# H4_PadController_Rev_2.net
KiCad netlist of a schematic drawn in EAGLE
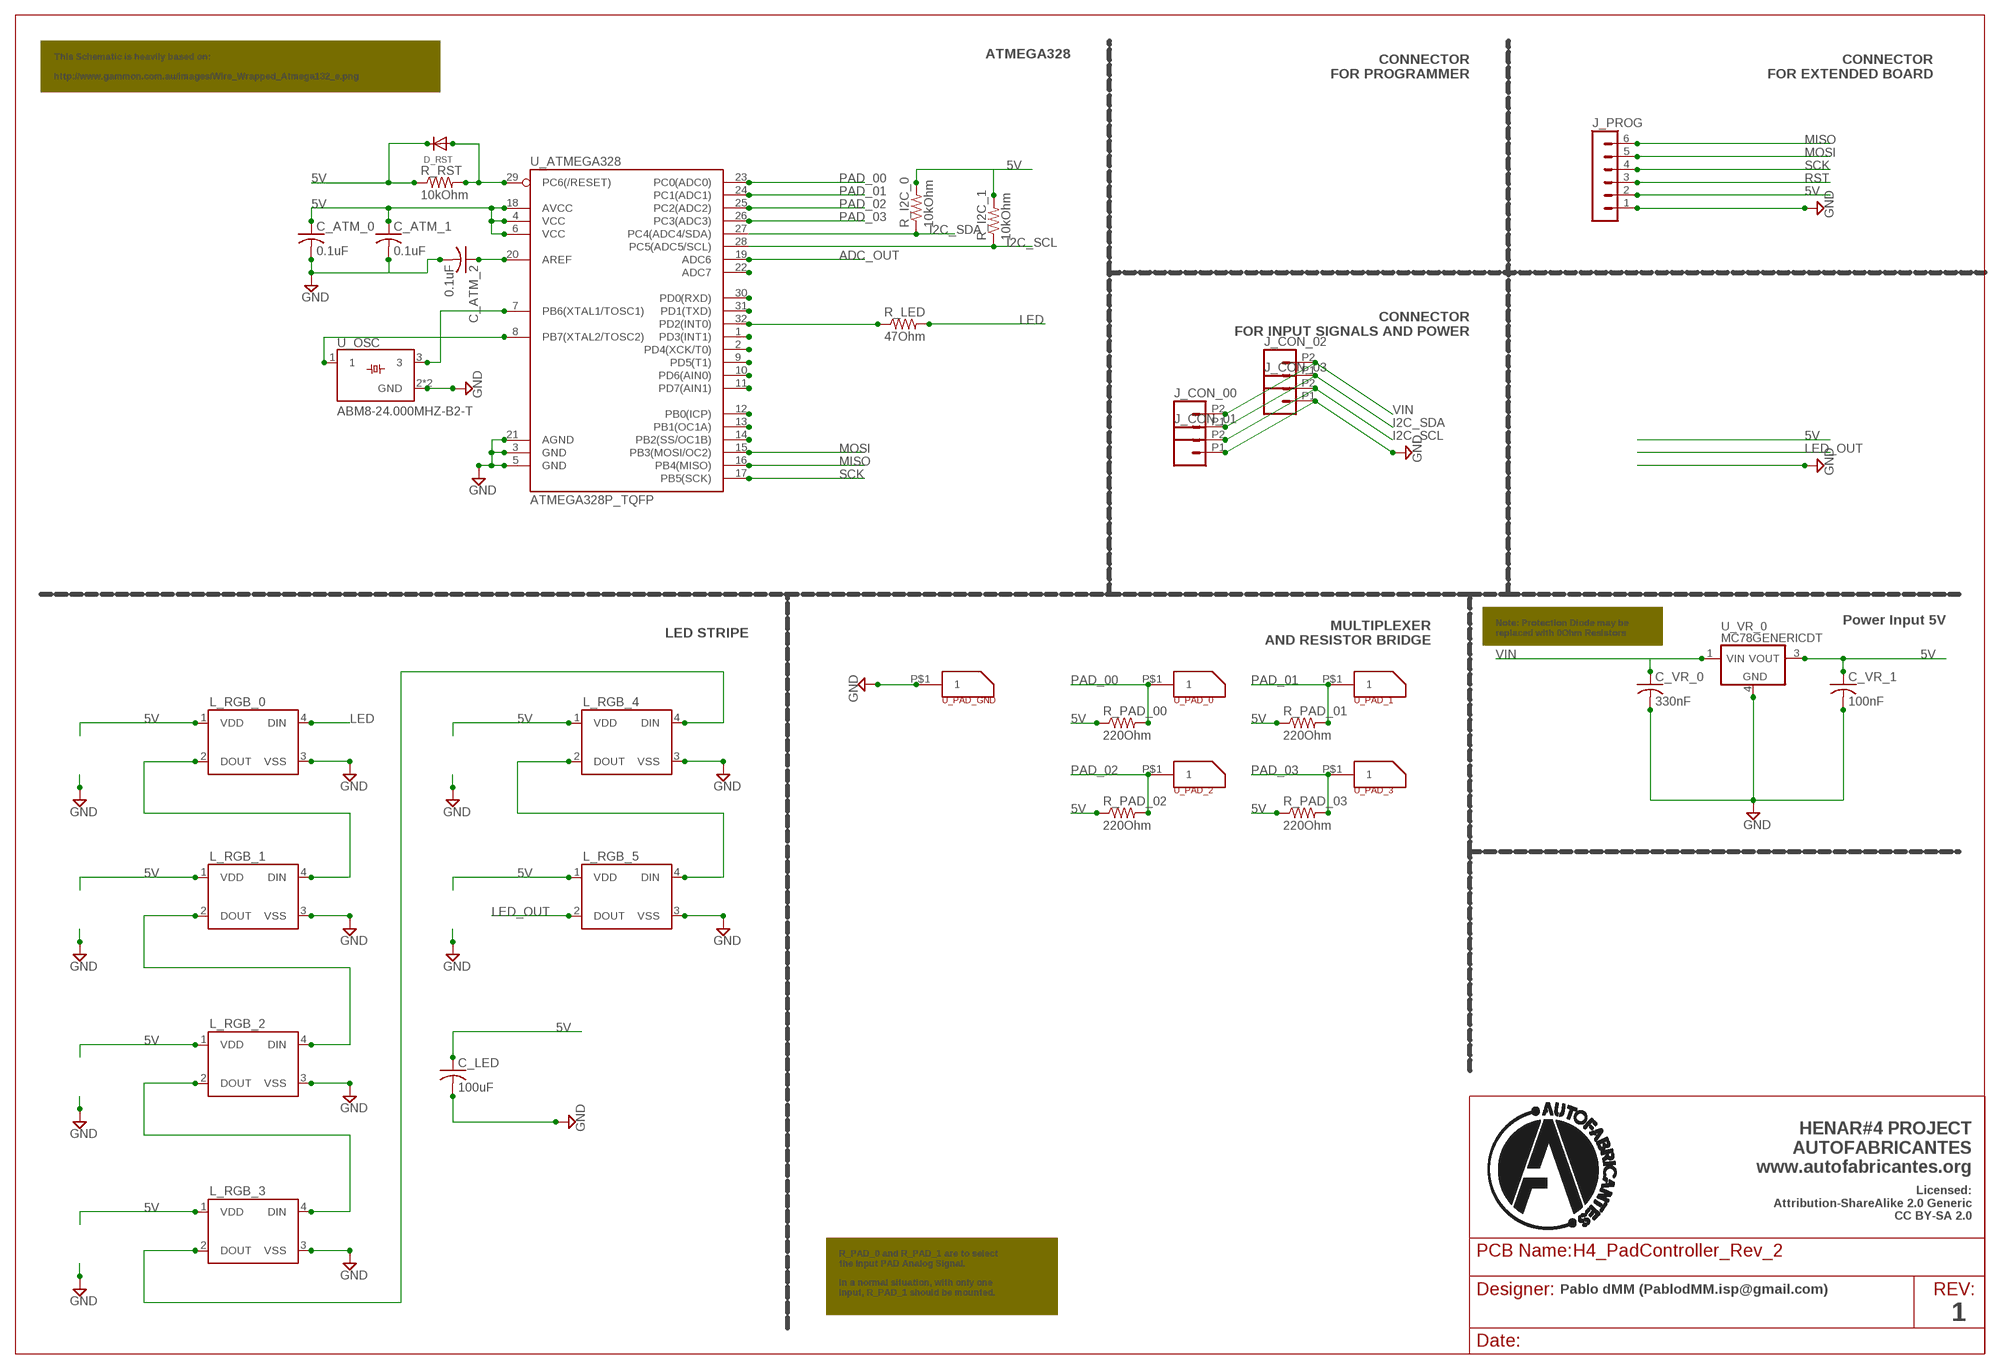
[diagram p0: schematic, sheet 1]

(export (version "E")
  (design (tool "Eeschema 10.0.6"))
  (components
    (comp (ref "C_ATM_0")
      (value "0.1uF")
      (footprint "eagle-import:C0805")
      (libsource (lib "eagle-import") (part "C-USC0805"))
    )
    (comp (ref "C_ATM_1")
      (value "0.1uF")
      (footprint "eagle-import:C0805")
      (libsource (lib "eagle-import") (part "C-USC0805"))
    )
    (comp (ref "C_ATM_2")
      (value "0.1uF")
      (footprint "eagle-import:C0805")
      (libsource (lib "eagle-import") (part "C-USC0805"))
    )
    (comp (ref "C_LED")
      (value "100uF")
      (footprint "eagle-import:C1210")
      (libsource (lib "eagle-import") (part "C-USC1210"))
    )
    (comp (ref "C_VR_0")
      (value "330nF")
      (footprint "eagle-import:C0805")
      (libsource (lib "eagle-import") (part "C-USC0805"))
    )
    (comp (ref "C_VR_1")
      (value "100nF")
      (footprint "eagle-import:C0805")
      (libsource (lib "eagle-import") (part "C-USC0805"))
    )
    (comp (ref "D_RST")
      (value "DIODESOD-123")
      (footprint "eagle-import:SOD-123")
      (libsource (lib "eagle-import") (part "DIODESOD-123"))
    )
    (comp (ref "J_CON_00")
      (value "M022.54MM_SCREWTERM")
      (footprint "eagle-import:1X02_2.54_SCREWTERM")
      (libsource (lib "eagle-import") (part "M022.54MM_SCREWTERM"))
    )
    (comp (ref "J_CON_01")
      (value "M022.54MM_SCREWTERM")
      (footprint "eagle-import:1X02_2.54_SCREWTERM")
      (libsource (lib "eagle-import") (part "M022.54MM_SCREWTERM"))
    )
    (comp (ref "J_CON_02")
      (value "M022.54MM_SCREWTERM")
      (footprint "eagle-import:1X02_2.54_SCREWTERM")
      (libsource (lib "eagle-import") (part "M022.54MM_SCREWTERM"))
    )
    (comp (ref "J_CON_03")
      (value "M022.54MM_SCREWTERM")
      (footprint "eagle-import:1X02_2.54_SCREWTERM")
      (libsource (lib "eagle-import") (part "M022.54MM_SCREWTERM"))
    )
    (comp (ref "J_PROG")
      (value "MA06-1")
      (footprint "eagle-import:MA06-1")
      (libsource (lib "eagle-import") (part "MA06-1"))
    )
    (comp (ref "L_RGB_0")
      (value "WS2812B")
      (footprint "eagle-import:WS2812B")
      (libsource (lib "eagle-import") (part "WS2812B"))
    )
    (comp (ref "L_RGB_1")
      (value "WS2812B")
      (footprint "eagle-import:WS2812B")
      (libsource (lib "eagle-import") (part "WS2812B"))
    )
    (comp (ref "L_RGB_2")
      (value "WS2812B")
      (footprint "eagle-import:WS2812B")
      (libsource (lib "eagle-import") (part "WS2812B"))
    )
    (comp (ref "L_RGB_3")
      (value "WS2812B")
      (footprint "eagle-import:WS2812B")
      (libsource (lib "eagle-import") (part "WS2812B"))
    )
    (comp (ref "L_RGB_4")
      (value "WS2812B")
      (footprint "eagle-import:WS2812B")
      (libsource (lib "eagle-import") (part "WS2812B"))
    )
    (comp (ref "L_RGB_5")
      (value "WS2812B")
      (footprint "eagle-import:WS2812B")
      (libsource (lib "eagle-import") (part "WS2812B"))
    )
    (comp (ref "R_I2C_0")
      (value "10kOhm")
      (footprint "eagle-import:M0805")
      (libsource (lib "eagle-import") (part "R-US_M0805"))
    )
    (comp (ref "R_I2C_1")
      (value "10kOhm")
      (footprint "eagle-import:M0805")
      (libsource (lib "eagle-import") (part "R-US_M0805"))
    )
    (comp (ref "R_LED")
      (value "47Ohm")
      (footprint "eagle-import:M0805")
      (libsource (lib "eagle-import") (part "R-US_M0805"))
    )
    (comp (ref "R_PAD_00")
      (value "220Ohm")
      (footprint "eagle-import:M0805")
      (libsource (lib "eagle-import") (part "R-US_M0805"))
    )
    (comp (ref "R_PAD_01")
      (value "220Ohm")
      (footprint "eagle-import:M0805")
      (libsource (lib "eagle-import") (part "R-US_M0805"))
    )
    (comp (ref "R_PAD_02")
      (value "220Ohm")
      (footprint "eagle-import:M0805")
      (libsource (lib "eagle-import") (part "R-US_M0805"))
    )
    (comp (ref "R_PAD_03")
      (value "220Ohm")
      (footprint "eagle-import:M0805")
      (libsource (lib "eagle-import") (part "R-US_M0805"))
    )
    (comp (ref "R_RST")
      (value "10kOhm")
      (footprint "eagle-import:M0805")
      (libsource (lib "eagle-import") (part "R-US_M0805"))
    )
    (comp (ref "U_ATMEGA328")
      (value "ATMEGA328P_TQFP")
      (footprint "eagle-import:TQFP32-08")
      (libsource (lib "eagle-import") (part "ATMEGA328P_TQFP"))
    )
    (comp (ref "U_OSC")
      (value "ABM8-24.000MHZ-B2-T")
      (footprint "eagle-import:OSCSC320X250X100N")
      (fields (field (name "MF") "Abracon"))
      (libsource (lib "eagle-import") (part "ABM8-24.000MHZ-B2-T"))
    )
    (comp (ref "U_PAD_0")
      (value "PAD_CONNECTOR_MULTI")
      (footprint "eagle-import:PAD_CONNECTOR_MULTI")
      (libsource (lib "eagle-import") (part "PAD_CONNECTOR_MULTI"))
    )
    (comp (ref "U_PAD_1")
      (value "PAD_CONNECTOR_MULTI")
      (footprint "eagle-import:PAD_CONNECTOR_MULTI")
      (libsource (lib "eagle-import") (part "PAD_CONNECTOR_MULTI"))
    )
    (comp (ref "U_PAD_2")
      (value "PAD_CONNECTOR_MULTI")
      (footprint "eagle-import:PAD_CONNECTOR_MULTI")
      (libsource (lib "eagle-import") (part "PAD_CONNECTOR_MULTI"))
    )
    (comp (ref "U_PAD_3")
      (value "PAD_CONNECTOR_MULTI")
      (footprint "eagle-import:PAD_CONNECTOR_MULTI")
      (libsource (lib "eagle-import") (part "PAD_CONNECTOR_MULTI"))
    )
    (comp (ref "U_PAD_GND")
      (value "PAD_CONNECTOR_MULTI")
      (footprint "eagle-import:PAD_CONNECTOR_MULTI")
      (libsource (lib "eagle-import") (part "PAD_CONNECTOR_MULTI"))
    )
    (comp (ref "U_VR_0")
      (value "MC78GENERICDT")
      (footprint "eagle-import:DPAK-3")
      (libsource (lib "eagle-import") (part "MC78DTGENERIC"))
    )
  )
  (nets
    (net (code "1") (name "/5V") (class "Default")
      (node (ref "C_ATM_0") (pin "1") (pinfunction "1_1") (pintype "passive"))
      (node (ref "C_ATM_1") (pin "1") (pinfunction "1_1") (pintype "passive"))
      (node (ref "C_LED") (pin "1") (pinfunction "1_1") (pintype "passive"))
      (node (ref "C_VR_1") (pin "1") (pinfunction "1_1") (pintype "passive"))
      (node (ref "D_RST") (pin "C") (pinfunction "C_C") (pintype "passive"))
      (node (ref "J_PROG") (pin "2") (pinfunction "2_2") (pintype "passive"))
      (node (ref "L_RGB_0") (pin "1") (pinfunction "VDD_1") (pintype "power_in"))
      (node (ref "L_RGB_1") (pin "1") (pinfunction "VDD_1") (pintype "power_in"))
      (node (ref "L_RGB_2") (pin "1") (pinfunction "VDD_1") (pintype "power_in"))
      (node (ref "L_RGB_3") (pin "1") (pinfunction "VDD_1") (pintype "power_in"))
      (node (ref "L_RGB_4") (pin "1") (pinfunction "VDD_1") (pintype "power_in"))
      (node (ref "L_RGB_5") (pin "1") (pinfunction "VDD_1") (pintype "power_in"))
      (node (ref "R_I2C_0") (pin "2") (pinfunction "2_2") (pintype "passive"))
      (node (ref "R_I2C_1") (pin "2") (pinfunction "2_2") (pintype "passive"))
      (node (ref "R_PAD_00") (pin "1") (pinfunction "1_1") (pintype "passive"))
      (node (ref "R_PAD_01") (pin "1") (pinfunction "1_1") (pintype "passive"))
      (node (ref "R_PAD_02") (pin "1") (pinfunction "1_1") (pintype "passive"))
      (node (ref "R_PAD_03") (pin "1") (pinfunction "1_1") (pintype "passive"))
      (node (ref "R_RST") (pin "1") (pinfunction "1_1") (pintype "passive"))
      (node (ref "U_ATMEGA328") (pin "18") (pinfunction "AVCC_18") (pintype "bidirectional"))
      (node (ref "U_ATMEGA328") (pin "4") (pinfunction "VCC_4") (pintype "bidirectional"))
      (node (ref "U_ATMEGA328") (pin "6") (pinfunction "VCC_6") (pintype "bidirectional"))
      (node (ref "U_VR_0") (pin "3") (pinfunction "VOUT_3") (pintype "power_in"))
    )
    (net (code "2") (name "/ADC_OUT") (class "Default")
      (node (ref "U_ATMEGA328") (pin "19") (pinfunction "ADC6_19") (pintype "bidirectional"))
    )
    (net (code "3") (name "/I2C_SCL") (class "Default")
      (node (ref "J_CON_01") (pin "P2") (pinfunction "2_P2") (pintype "passive"))
      (node (ref "J_CON_03") (pin "P2") (pinfunction "2_P2") (pintype "passive"))
      (node (ref "R_I2C_1") (pin "1") (pinfunction "1_1") (pintype "passive"))
      (node (ref "U_ATMEGA328") (pin "28") (pinfunction "PC5(ADC5/SCL)_28") (pintype "bidirectional"))
    )
    (net (code "4") (name "/I2C_SDA") (class "Default")
      (node (ref "J_CON_00") (pin "P1") (pinfunction "1_P1") (pintype "passive"))
      (node (ref "J_CON_02") (pin "P1") (pinfunction "1_P1") (pintype "passive"))
      (node (ref "R_I2C_0") (pin "1") (pinfunction "1_1") (pintype "passive"))
      (node (ref "U_ATMEGA328") (pin "27") (pinfunction "PC4(ADC4/SDA)_27") (pintype "bidirectional"))
    )
    (net (code "5") (name "/LED") (class "Default")
      (node (ref "L_RGB_0") (pin "4") (pinfunction "DIN_4") (pintype "input"))
      (node (ref "R_LED") (pin "2") (pinfunction "2_2") (pintype "passive"))
    )
    (net (code "6") (name "/LED_OUT") (class "Default")
      (node (ref "L_RGB_5") (pin "2") (pinfunction "DOUT_2") (pintype "output"))
    )
    (net (code "7") (name "/MISO") (class "Default")
      (node (ref "J_PROG") (pin "6") (pinfunction "6_6") (pintype "passive"))
      (node (ref "U_ATMEGA328") (pin "16") (pinfunction "PB4(MISO)_16") (pintype "bidirectional"))
    )
    (net (code "8") (name "/MOSI") (class "Default")
      (node (ref "J_PROG") (pin "5") (pinfunction "5_5") (pintype "passive"))
      (node (ref "U_ATMEGA328") (pin "15") (pinfunction "PB3(MOSI/OC2)_15") (pintype "bidirectional"))
    )
    (net (code "9") (name "/PAD_00") (class "Default")
      (node (ref "R_PAD_00") (pin "2") (pinfunction "2_2") (pintype "passive"))
      (node (ref "U_ATMEGA328") (pin "23") (pinfunction "PC0(ADC0)_23") (pintype "bidirectional"))
      (node (ref "U_PAD_0") (pin "P$1") (pinfunction "1_P$1") (pintype "bidirectional"))
    )
    (net (code "10") (name "/PAD_01") (class "Default")
      (node (ref "R_PAD_01") (pin "2") (pinfunction "2_2") (pintype "passive"))
      (node (ref "U_ATMEGA328") (pin "24") (pinfunction "PC1(ADC1)_24") (pintype "bidirectional"))
      (node (ref "U_PAD_1") (pin "P$1") (pinfunction "1_P$1") (pintype "bidirectional"))
    )
    (net (code "11") (name "/PAD_02") (class "Default")
      (node (ref "R_PAD_02") (pin "2") (pinfunction "2_2") (pintype "passive"))
      (node (ref "U_ATMEGA328") (pin "25") (pinfunction "PC2(ADC2)_25") (pintype "bidirectional"))
      (node (ref "U_PAD_2") (pin "P$1") (pinfunction "1_P$1") (pintype "bidirectional"))
    )
    (net (code "12") (name "/PAD_03") (class "Default")
      (node (ref "R_PAD_03") (pin "2") (pinfunction "2_2") (pintype "passive"))
      (node (ref "U_ATMEGA328") (pin "26") (pinfunction "PC3(ADC3)_26") (pintype "bidirectional"))
      (node (ref "U_PAD_3") (pin "P$1") (pinfunction "1_P$1") (pintype "bidirectional"))
    )
    (net (code "13") (name "/RST") (class "Default")
      (node (ref "D_RST") (pin "A") (pinfunction "A_A") (pintype "passive"))
      (node (ref "J_PROG") (pin "3") (pinfunction "3_3") (pintype "passive"))
      (node (ref "R_RST") (pin "2") (pinfunction "2_2") (pintype "passive"))
      (node (ref "U_ATMEGA328") (pin "29") (pinfunction "PC6(/RESET)_29") (pintype "bidirectional"))
    )
    (net (code "14") (name "/SCK") (class "Default")
      (node (ref "J_PROG") (pin "4") (pinfunction "4_4") (pintype "passive"))
      (node (ref "U_ATMEGA328") (pin "17") (pinfunction "PB5(SCK)_17") (pintype "bidirectional"))
    )
    (net (code "15") (name "/VIN") (class "Default")
      (node (ref "C_VR_0") (pin "1") (pinfunction "1_1") (pintype "passive"))
      (node (ref "J_CON_00") (pin "P2") (pinfunction "2_P2") (pintype "passive"))
      (node (ref "J_CON_02") (pin "P2") (pinfunction "2_P2") (pintype "passive"))
      (node (ref "U_VR_0") (pin "1") (pinfunction "VIN_1") (pintype "power_in"))
    )
    (net (code "16") (name "GND") (class "Default")
      (node (ref "C_ATM_0") (pin "2") (pinfunction "2_2") (pintype "passive"))
      (node (ref "C_ATM_1") (pin "2") (pinfunction "2_2") (pintype "passive"))
      (node (ref "C_ATM_2") (pin "2") (pinfunction "2_2") (pintype "passive"))
      (node (ref "C_LED") (pin "2") (pinfunction "2_2") (pintype "passive"))
      (node (ref "C_VR_0") (pin "2") (pinfunction "2_2") (pintype "passive"))
      (node (ref "C_VR_1") (pin "2") (pinfunction "2_2") (pintype "passive"))
      (node (ref "J_CON_01") (pin "P1") (pinfunction "1_P1") (pintype "passive"))
      (node (ref "J_CON_03") (pin "P1") (pinfunction "1_P1") (pintype "passive"))
      (node (ref "J_PROG") (pin "1") (pinfunction "1_1") (pintype "passive"))
      (node (ref "L_RGB_0") (pin "3") (pinfunction "VSS_3") (pintype "power_in"))
      (node (ref "L_RGB_1") (pin "3") (pinfunction "VSS_3") (pintype "power_in"))
      (node (ref "L_RGB_2") (pin "3") (pinfunction "VSS_3") (pintype "power_in"))
      (node (ref "L_RGB_3") (pin "3") (pinfunction "VSS_3") (pintype "power_in"))
      (node (ref "L_RGB_4") (pin "3") (pinfunction "VSS_3") (pintype "power_in"))
      (node (ref "L_RGB_5") (pin "3") (pinfunction "VSS_3") (pintype "power_in"))
      (node (ref "U_ATMEGA328") (pin "21") (pinfunction "AGND_21") (pintype "bidirectional"))
      (node (ref "U_ATMEGA328") (pin "3") (pinfunction "GND_3") (pintype "bidirectional"))
      (node (ref "U_ATMEGA328") (pin "5") (pinfunction "GND_5") (pintype "bidirectional"))
      (node (ref "U_OSC") (pin "2") (pinfunction "GND_2") (pintype "power_in"))
      (node (ref "U_OSC") (pin "4") (pinfunction "GND_4") (pintype "power_in"))
      (node (ref "U_PAD_GND") (pin "P$1") (pinfunction "1_P$1") (pintype "bidirectional"))
      (node (ref "U_VR_0") (pin "4") (pinfunction "GND_4") (pintype "power_in"))
    )
    (net (code "17") (name "Net-(L_RGB_0-DOUT)") (class "Default")
      (node (ref "L_RGB_0") (pin "2") (pinfunction "DOUT_2") (pintype "output"))
      (node (ref "L_RGB_1") (pin "4") (pinfunction "DIN_4") (pintype "input"))
    )
    (net (code "18") (name "Net-(L_RGB_1-DOUT)") (class "Default")
      (node (ref "L_RGB_1") (pin "2") (pinfunction "DOUT_2") (pintype "output"))
      (node (ref "L_RGB_2") (pin "4") (pinfunction "DIN_4") (pintype "input"))
    )
    (net (code "19") (name "Net-(L_RGB_2-DOUT)") (class "Default")
      (node (ref "L_RGB_2") (pin "2") (pinfunction "DOUT_2") (pintype "output"))
      (node (ref "L_RGB_3") (pin "4") (pinfunction "DIN_4") (pintype "input"))
    )
    (net (code "20") (name "Net-(L_RGB_3-DOUT)") (class "Default")
      (node (ref "L_RGB_3") (pin "2") (pinfunction "DOUT_2") (pintype "output"))
      (node (ref "L_RGB_4") (pin "4") (pinfunction "DIN_4") (pintype "input"))
    )
    (net (code "21") (name "Net-(L_RGB_4-DOUT)") (class "Default")
      (node (ref "L_RGB_4") (pin "2") (pinfunction "DOUT_2") (pintype "output"))
      (node (ref "L_RGB_5") (pin "4") (pinfunction "DIN_4") (pintype "input"))
    )
    (net (code "22") (name "Net-(U_ATMEGA328-AREF)") (class "Default")
      (node (ref "C_ATM_2") (pin "1") (pinfunction "1_1") (pintype "passive"))
      (node (ref "U_ATMEGA328") (pin "20") (pinfunction "AREF_20") (pintype "bidirectional"))
    )
    (net (code "23") (name "Net-(U_ATMEGA328-PB6(XTAL1{slash}TOSC1))") (class "Default")
      (node (ref "U_ATMEGA328") (pin "7") (pinfunction "PB6(XTAL1/TOSC1)_7") (pintype "bidirectional"))
      (node (ref "U_OSC") (pin "3") (pinfunction "3_3") (pintype "passive"))
    )
    (net (code "24") (name "Net-(U_ATMEGA328-PB7(XTAL2{slash}TOSC2))") (class "Default")
      (node (ref "U_ATMEGA328") (pin "8") (pinfunction "PB7(XTAL2/TOSC2)_8") (pintype "bidirectional"))
      (node (ref "U_OSC") (pin "1") (pinfunction "1_1") (pintype "passive"))
    )
    (net (code "25") (name "Net-(U_ATMEGA328-PD2(INT0))") (class "Default")
      (node (ref "R_LED") (pin "1") (pinfunction "1_1") (pintype "passive"))
      (node (ref "U_ATMEGA328") (pin "32") (pinfunction "PD2(INT0)_32") (pintype "bidirectional"))
    )
    (net (code "26") (name "unconnected-(U_ATMEGA328-ADC7-Pad22)") (class "Default")
      (node (ref "U_ATMEGA328") (pin "22") (pinfunction "ADC7_22") (pintype "bidirectional"))
    )
    (net (code "27") (name "unconnected-(U_ATMEGA328-PB0(ICP)-Pad12)") (class "Default")
      (node (ref "U_ATMEGA328") (pin "12") (pinfunction "PB0(ICP)_12") (pintype "bidirectional"))
    )
    (net (code "28") (name "unconnected-(U_ATMEGA328-PB1(OC1A)-Pad13)") (class "Default")
      (node (ref "U_ATMEGA328") (pin "13") (pinfunction "PB1(OC1A)_13") (pintype "bidirectional"))
    )
    (net (code "29") (name "unconnected-(U_ATMEGA328-PB2(SS{slash}OC1B)-Pad14)") (class "Default")
      (node (ref "U_ATMEGA328") (pin "14") (pinfunction "PB2(SS/OC1B)_14") (pintype "bidirectional"))
    )
    (net (code "30") (name "unconnected-(U_ATMEGA328-PD0(RXD)-Pad30)") (class "Default")
      (node (ref "U_ATMEGA328") (pin "30") (pinfunction "PD0(RXD)_30") (pintype "bidirectional"))
    )
    (net (code "31") (name "unconnected-(U_ATMEGA328-PD1(TXD)-Pad31)") (class "Default")
      (node (ref "U_ATMEGA328") (pin "31") (pinfunction "PD1(TXD)_31") (pintype "bidirectional"))
    )
    (net (code "32") (name "unconnected-(U_ATMEGA328-PD3(INT1)-Pad1)") (class "Default")
      (node (ref "U_ATMEGA328") (pin "1") (pinfunction "PD3(INT1)_1") (pintype "bidirectional"))
    )
    (net (code "33") (name "unconnected-(U_ATMEGA328-PD4(XCK{slash}T0)-Pad2)") (class "Default")
      (node (ref "U_ATMEGA328") (pin "2") (pinfunction "PD4(XCK/T0)_2") (pintype "bidirectional"))
    )
    (net (code "34") (name "unconnected-(U_ATMEGA328-PD5(T1)-Pad9)") (class "Default")
      (node (ref "U_ATMEGA328") (pin "9") (pinfunction "PD5(T1)_9") (pintype "bidirectional"))
    )
    (net (code "35") (name "unconnected-(U_ATMEGA328-PD6(AIN0)-Pad10)") (class "Default")
      (node (ref "U_ATMEGA328") (pin "10") (pinfunction "PD6(AIN0)_10") (pintype "bidirectional"))
    )
    (net (code "36") (name "unconnected-(U_ATMEGA328-PD7(AIN1)-Pad11)") (class "Default")
      (node (ref "U_ATMEGA328") (pin "11") (pinfunction "PD7(AIN1)_11") (pintype "bidirectional"))
    )
  )
)
